# HB100_and_neo_m6.net
KiCad netlist of a schematic drawn in Altium Designer
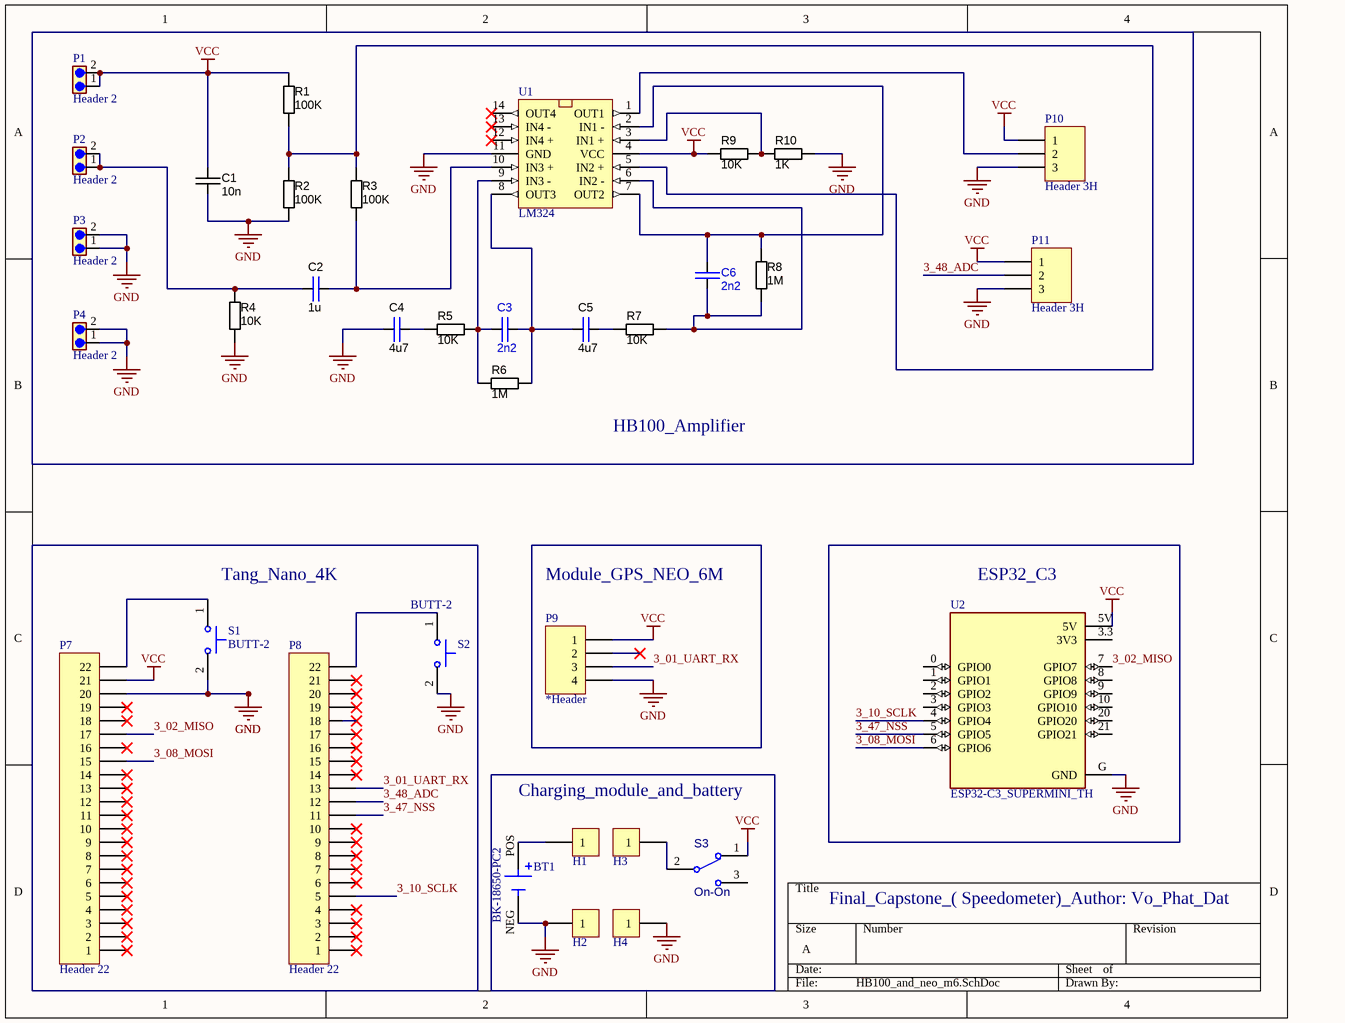
[diagram p0: HB100_and_neo_m6.SchDoc]

(export (version "E")
  (design (tool "Eeschema 10.0.6"))
  (components
    (comp (ref "BT1")
      (value "BK-18650-PC2")
      (footprint "BAT_BK-18650-PC2")
      (description "Battery Holder (Open) 18650 1 Cell PC Pin")
      (fields (field (name "MF") "MPD (Memory"))
      (libsource (lib "BK-18650-PC2") (part "BK-18650-PC2"))
    )
    (comp (ref "C1")
      (value "10n")
      (footprint "CAPC500P450250X550")
      (description "Capacitor Ceramic 220nF 10% 50V X7R radial 5mm lead spacing")
      (fields (field (name "TOLERANCE") "±10%") (field (name "Comment") "approved sub OK"))
      (libsource (lib "my Library") (part "CAPR_220n_Radial_5mm"))
    )
    (comp (ref "C2")
      (value "1u")
      (footprint "CAPC3216X180N")
      (description "Capacitor SMD Cer 220nF 10% 16V X7R 1206")
      (fields (field (name "TOLERANCE") "±10%") (field (name "Comment") "approved sub OK"))
      (libsource (lib "My library altium") (part "CAP C_1206"))
    )
    (comp (ref "C3")
      (value "2n2")
      (footprint "CAPC2012X135N")
      (description "Capacitor SMD Cer 1.8nF 10% 50V X7R 0805")
      (fields (field (name "TOLERANCE") "±10%") (field (name "Comment") "approved sub OK"))
      (libsource (lib "My library altium") (part "CAP C_0805"))
    )
    (comp (ref "C4")
      (value "4u7")
      (footprint "CAPC3216X180N")
      (description "Capacitor SMD Cer 220nF 10% 16V X7R 1206")
      (fields (field (name "TOLERANCE") "±10%") (field (name "Comment") "approved sub OK"))
      (libsource (lib "My library altium") (part "CAP C_1206"))
    )
    (comp (ref "C5")
      (value "4u7")
      (footprint "CAPC3216X180N")
      (description "Capacitor SMD Cer 220nF 10% 16V X7R 1206")
      (fields (field (name "TOLERANCE") "±10%") (field (name "Comment") "approved sub OK"))
      (libsource (lib "My library altium") (part "CAP C_1206"))
    )
    (comp (ref "C6")
      (value "2n2")
      (footprint "CAPC2012X135N")
      (description "Capacitor SMD Cer 1.8nF 10% 50V X7R 0805")
      (fields (field (name "TOLERANCE") "±10%") (field (name "Comment") "approved sub OK"))
      (libsource (lib "My library altium") (part "CAP C_0805"))
    )
    (comp (ref "H1")
      (value "Header 1")
      (footprint "HEAD1")
      (description "Header, 1-Pin, Right Angle")
      (fields (field (name "PUBLISHER") "Cynetik Group"))
      (libsource (lib "") (part "Header 1_1"))
    )
    (comp (ref "H2")
      (value "Header 1")
      (footprint "HEAD1")
      (description "Header, 1-Pin, Right Angle")
      (fields (field (name "PUBLISHER") "Cynetik Group"))
      (libsource (lib "") (part "Header 1_1"))
    )
    (comp (ref "H3")
      (value "Header 1")
      (footprint "HEAD1")
      (description "Header, 1-Pin, Right Angle")
      (fields (field (name "PUBLISHER") "Cynetik Group"))
      (libsource (lib "Cty1") (part "Header 1"))
    )
    (comp (ref "H4")
      (value "Header 1")
      (footprint "HEAD1")
      (description "Header, 1-Pin, Right Angle")
      (fields (field (name "PUBLISHER") "Cynetik Group"))
      (libsource (lib "Cty1") (part "Header 1"))
    )
    (comp (ref "P1")
      (value "Header 2")
      (footprint "61300211121")
      (fields (field (name "MF") "{'manufacturer': u'Wurth Electronics'}") (field (name "MP") "61300211121"))
      (libsource (lib "6130XX11121_61300211121") (part "6130XX11121_61300211121"))
    )
    (comp (ref "P2")
      (value "Header 2")
      (footprint "61300211121")
      (fields (field (name "MF") "{'manufacturer': u'Wurth Electronics'}") (field (name "MP") "61300211121"))
      (libsource (lib "6130XX11121_61300211121") (part "6130XX11121_61300211121"))
    )
    (comp (ref "P3")
      (value "Header 2")
      (footprint "61300211121")
      (fields (field (name "MF") "{'manufacturer': u'Wurth Electronics'}") (field (name "MP") "61300211121"))
      (libsource (lib "6130XX11121_61300211121") (part "6130XX11121_61300211121"))
    )
    (comp (ref "P4")
      (value "Header 2")
      (footprint "61300211121")
      (fields (field (name "MF") "{'manufacturer': u'Wurth Electronics'}") (field (name "MP") "61300211121"))
      (libsource (lib "6130XX11121_61300211121") (part "6130XX11121_61300211121"))
    )
    (comp (ref "P7")
      (value "Header 22")
      (footprint "HDR1X22")
      (description "Header, 22-Pin")
      (fields (field (name "PUBLISHER") "Altium Limited"))
      (libsource (lib "my Library") (part "Header 22"))
    )
    (comp (ref "P8")
      (value "Header 22")
      (footprint "HDR1X22")
      (description "Header, 22-Pin")
      (fields (field (name "PUBLISHER") "Altium Limited"))
      (libsource (lib "my Library") (part "Header 22"))
    )
    (comp (ref "P9")
      (value "*Header")
      (footprint "HDR1X4")
      (description "Header, 4-Pin, Right Angle")
      (fields (field (name "PUBLISHER") "Altium Limited"))
      (libsource (lib "Cty1") (part "Header 4"))
    )
    (comp (ref "P10")
      (value "Header 3H")
      (footprint "HDR1X3H")
      (description "Header, 3-Pin, Right Angle")
      (fields (field (name "PUBLISHER") "Altium Limited"))
      (libsource (lib "Cty1") (part "Header 3H"))
    )
    (comp (ref "P11")
      (value "Header 3H")
      (footprint "HDR1X3H")
      (description "Header, 3-Pin, Right Angle")
      (fields (field (name "PUBLISHER") "Altium Limited"))
      (libsource (lib "Cty1") (part "Header 3H"))
    )
    (comp (ref "R1")
      (value "100K")
      (footprint "RESC3216N_ZERO")
      (description "Resistor SMD chip 0.0 Ohm 0.25W 1206")
      (fields (field (name "TOLERANCE") "±5%") (field (name "Comment") "Thick Film"))
      (libsource (lib "My library altium") (part "RES_1206"))
    )
    (comp (ref "R2")
      (value "100K")
      (footprint "RESC3216N_ZERO")
      (description "Resistor SMD chip 0.0 Ohm 0.25W 1206")
      (fields (field (name "TOLERANCE") "±5%") (field (name "Comment") "Thick Film"))
      (libsource (lib "My library altium") (part "RES_1206"))
    )
    (comp (ref "R3")
      (value "100K")
      (footprint "RESC3216N_ZERO")
      (description "Resistor SMD chip 0.0 Ohm 0.25W 1206")
      (fields (field (name "TOLERANCE") "±5%") (field (name "Comment") "Thick Film"))
      (libsource (lib "My library altium") (part "RES_1206"))
    )
    (comp (ref "R4")
      (value "10K")
      (footprint "RESC3216N_ZERO")
      (description "Resistor SMD chip 0.0 Ohm 0.25W 1206")
      (fields (field (name "TOLERANCE") "±5%") (field (name "Comment") "Thick Film"))
      (libsource (lib "My library altium") (part "RES_1206"))
    )
    (comp (ref "R5")
      (value "10K")
      (footprint "RESC3216N_ZERO")
      (description "Resistor SMD chip 0.0 Ohm 0.25W 1206")
      (fields (field (name "TOLERANCE") "±5%") (field (name "Comment") "Thick Film"))
      (libsource (lib "") (part "RES_1206_1"))
    )
    (comp (ref "R6")
      (value "1M")
      (footprint "RESC3216N_ZERO")
      (description "Resistor SMD chip 0.0 Ohm 0.25W 1206")
      (fields (field (name "TOLERANCE") "±5%") (field (name "Comment") "Thick Film"))
      (libsource (lib "") (part "RES_1206_1"))
    )
    (comp (ref "R7")
      (value "10K")
      (footprint "RESC3216N_ZERO")
      (description "Resistor SMD chip 0.0 Ohm 0.25W 1206")
      (fields (field (name "TOLERANCE") "±5%") (field (name "Comment") "Thick Film"))
      (libsource (lib "") (part "RES_1206_1"))
    )
    (comp (ref "R8")
      (value "1M")
      (footprint "RESC3216N_ZERO")
      (description "Resistor SMD chip 0.0 Ohm 0.25W 1206")
      (fields (field (name "TOLERANCE") "±5%") (field (name "Comment") "Thick Film"))
      (libsource (lib "") (part "RES_1206_2"))
    )
    (comp (ref "R9")
      (value "10K")
      (footprint "RESC3216N_ZERO")
      (description "Resistor SMD chip 0.0 Ohm 0.25W 1206")
      (fields (field (name "TOLERANCE") "±5%") (field (name "Comment") "Thick Film"))
      (libsource (lib "") (part "RES_1206_1"))
    )
    (comp (ref "R10")
      (value "1K")
      (footprint "RESC3216N_ZERO")
      (description "Resistor SMD chip 0.0 Ohm 0.25W 1206")
      (fields (field (name "TOLERANCE") "±5%") (field (name "Comment") "Thick Film"))
      (libsource (lib "") (part "RES_1206_1"))
    )
    (comp (ref "S1")
      (value "BUTT-2")
      (footprint "SW_BUTT-2")
      (description "Tactile Switches MINI PUSH BUTTON SWITCH 2-PIN QTY. 4")
      (fields (field (name "MF") "Gravitech"))
      (libsource (lib "BUTT-2") (part "BUTT-2"))
    )
    (comp (ref "S2")
      (value "BUTT-2")
      (footprint "SW_BUTT-2")
      (description "Tactile Switches MINI PUSH BUTTON SWITCH 2-PIN QTY. 4")
      (fields (field (name "MF") "Gravitech"))
      (libsource (lib "BUTT-2") (part "BUTT-2"))
    )
    (comp (ref "S3")
      (value "ON-ON")
      (footprint "SWITCH_SPDT_SLIDER")
      (description "Switch THD vertical toggle SPDT")
      (fields (field (name "SWITCH FUNCTION") "On-On"))
      (libsource (lib "my Library") (part "SW_THD_SPDT_On-On"))
    )
    (comp (ref "U1")
      (value "LM324")
      (footprint "SOIC127P600X175-14N-LM324")
      (libsource (lib "My library altium") (part "LM324"))
    )
    (comp (ref "U2")
      (value "ESP32-C3_SUPERMINI_TH")
      (footprint "MODULE_ESP32-C3_SUPERMINI_TH")
      (description "Super tiny ESP32-C3 board")
      (fields (field (name "MF") "Espressif Systems") (field (name "MP") "ESP32-C3 SuperMini_TH"))
      (libsource (lib "ESP32-C3_SUPERMINI_TH") (part "ESP32-C3_SUPERMINI_TH"))
    )
  )
  (nets
    (net (code "1") (name "/3_01_UART_RX") (class "Default")
      (node (ref "P8") (pin "13") (pinfunction "13_13") (pintype "passive"))
      (node (ref "P9") (pin "3") (pinfunction "3_3") (pintype "passive"))
    )
    (net (code "2") (name "/3_02_MISO") (class "Default")
      (node (ref "P7") (pin "17") (pinfunction "17_17") (pintype "passive"))
      (node (ref "U2") (pin "7") (pinfunction "GPIO7_7") (pintype "bidirectional"))
    )
    (net (code "3") (name "/3_08_MOSI") (class "Default")
      (node (ref "P7") (pin "15") (pinfunction "15_15") (pintype "passive"))
      (node (ref "U2") (pin "6") (pinfunction "GPIO6_6") (pintype "bidirectional"))
    )
    (net (code "4") (name "/3_10_SCLK") (class "Default")
      (node (ref "P8") (pin "5") (pinfunction "5_5") (pintype "passive"))
      (node (ref "U2") (pin "4") (pinfunction "GPIO4_4") (pintype "bidirectional"))
    )
    (net (code "5") (name "/3_47_NSS") (class "Default")
      (node (ref "P8") (pin "11") (pinfunction "11_11") (pintype "passive"))
      (node (ref "U2") (pin "5") (pinfunction "GPIO5_5") (pintype "bidirectional"))
    )
    (net (code "6") (name "/3_48_ADC") (class "Default")
      (node (ref "P11") (pin "2") (pinfunction "2_2") (pintype "passive"))
      (node (ref "P8") (pin "12") (pinfunction "12_12") (pintype "passive"))
    )
    (net (code "7") (name "GND") (class "Default")
      (node (ref "BT1") (pin "NEG") (pinfunction "NEG_NEG") (pintype "passive"))
      (node (ref "C1") (pin "1") (pintype "passive"))
      (node (ref "C4") (pin "1") (pintype "passive"))
      (node (ref "H2") (pin "1") (pinfunction "1_1") (pintype "passive"))
      (node (ref "H4") (pin "1") (pinfunction "1_1") (pintype "passive"))
      (node (ref "P10") (pin "3") (pinfunction "3_3") (pintype "passive"))
      (node (ref "P11") (pin "3") (pinfunction "3_3") (pintype "passive"))
      (node (ref "P3") (pin "1") (pinfunction "1_1") (pintype "passive"))
      (node (ref "P3") (pin "2") (pinfunction "2_2") (pintype "passive"))
      (node (ref "P4") (pin "1") (pinfunction "1_1") (pintype "passive"))
      (node (ref "P4") (pin "2") (pinfunction "2_2") (pintype "passive"))
      (node (ref "P7") (pin "20") (pinfunction "20_20") (pintype "passive"))
      (node (ref "P9") (pin "4") (pinfunction "4_4") (pintype "passive"))
      (node (ref "R10") (pin "2") (pinfunction "2_2") (pintype "passive"))
      (node (ref "R2") (pin "2") (pinfunction "2_2") (pintype "passive"))
      (node (ref "R4") (pin "2") (pinfunction "2_2") (pintype "passive"))
      (node (ref "S1") (pin "2") (pinfunction "2_2") (pintype "passive"))
      (node (ref "S2") (pin "2") (pinfunction "2_2") (pintype "passive"))
      (node (ref "U1") (pin "11") (pinfunction "GND_11") (pintype "power_in"))
      (node (ref "U2") (pin "G") (pinfunction "GND_G") (pintype "power_in"))
    )
    (net (code "8") (name "Net-(BT1-PadPOS)") (class "Default")
      (node (ref "BT1") (pin "POS") (pinfunction "POS_POS") (pintype "passive"))
      (node (ref "H1") (pin "1") (pinfunction "1_1") (pintype "passive"))
    )
    (net (code "9") (name "Net-(C2-Pad1)") (class "Default")
      (node (ref "C2") (pin "1") (pintype "passive"))
      (node (ref "P2") (pin "1") (pinfunction "1_1") (pintype "passive"))
      (node (ref "P2") (pin "2") (pinfunction "2_2") (pintype "passive"))
      (node (ref "R4") (pin "1") (pinfunction "1_1") (pintype "passive"))
    )
    (net (code "10") (name "Net-(C4-Pad2)") (class "Default")
      (node (ref "C4") (pin "2") (pintype "passive"))
      (node (ref "R5") (pin "1") (pinfunction "1_1") (pintype "passive"))
    )
    (net (code "11") (name "Net-(C5-Pad2)") (class "Default")
      (node (ref "C5") (pin "2") (pintype "passive"))
      (node (ref "R7") (pin "1") (pinfunction "1_1") (pintype "passive"))
    )
    (net (code "12") (name "Net-(H3-Pad1)") (class "Default")
      (node (ref "H3") (pin "1") (pinfunction "1_1") (pintype "passive"))
      (node (ref "S3") (pin "2") (pinfunction "2_2") (pintype "passive"))
    )
    (net (code "13") (name "Net-(P7-Pad22)") (class "Default")
      (node (ref "P7") (pin "22") (pinfunction "22_22") (pintype "passive"))
      (node (ref "S1") (pin "1") (pinfunction "1_1") (pintype "passive"))
    )
    (net (code "14") (name "Net-(P8-Pad22)") (class "Default")
      (node (ref "P8") (pin "22") (pinfunction "22_22") (pintype "passive"))
      (node (ref "S2") (pin "1") (pinfunction "1_1") (pintype "passive"))
    )
    (net (code "15") (name "Net-(U1-IN1_+)") (class "Default")
      (node (ref "R10") (pin "1") (pinfunction "1_1") (pintype "passive"))
      (node (ref "R9") (pin "2") (pinfunction "2_2") (pintype "passive"))
      (node (ref "U1") (pin "3") (pinfunction "IN1_+_3") (pintype "input"))
    )
    (net (code "16") (name "Net-(U1-IN1_-)") (class "Default")
      (node (ref "C6") (pin "1") (pintype "passive"))
      (node (ref "R8") (pin "2") (pinfunction "2_2") (pintype "passive"))
      (node (ref "U1") (pin "2") (pinfunction "IN1_-_2") (pintype "input"))
      (node (ref "U1") (pin "7") (pinfunction "OUT2_7") (pintype "output"))
    )
    (net (code "17") (name "Net-(U1-IN2_+)") (class "Default")
      (node (ref "R1") (pin "2") (pinfunction "2_2") (pintype "passive"))
      (node (ref "R2") (pin "1") (pinfunction "1_1") (pintype "passive"))
      (node (ref "R3") (pin "1") (pinfunction "1_1") (pintype "passive"))
      (node (ref "U1") (pin "5") (pinfunction "IN2_+_5") (pintype "input"))
    )
    (net (code "18") (name "Net-(U1-IN2_-)") (class "Default")
      (node (ref "C6") (pin "2") (pintype "passive"))
      (node (ref "R7") (pin "2") (pinfunction "2_2") (pintype "passive"))
      (node (ref "R8") (pin "1") (pinfunction "1_1") (pintype "passive"))
      (node (ref "U1") (pin "6") (pinfunction "IN2_-_6") (pintype "input"))
    )
    (net (code "19") (name "Net-(U1-IN3_+)") (class "Default")
      (node (ref "C2") (pin "2") (pintype "passive"))
      (node (ref "R3") (pin "2") (pinfunction "2_2") (pintype "passive"))
      (node (ref "U1") (pin "10") (pinfunction "IN3_+_10") (pintype "input"))
    )
    (net (code "20") (name "Net-(U1-IN3_-)") (class "Default")
      (node (ref "C3") (pin "1") (pintype "passive"))
      (node (ref "R5") (pin "2") (pinfunction "2_2") (pintype "passive"))
      (node (ref "R6") (pin "1") (pinfunction "1_1") (pintype "passive"))
      (node (ref "U1") (pin "9") (pinfunction "IN3_-_9") (pintype "input"))
    )
    (net (code "21") (name "Net-(U1-OUT1)") (class "Default")
      (node (ref "P10") (pin "2") (pinfunction "2_2") (pintype "passive"))
      (node (ref "U1") (pin "1") (pinfunction "OUT1_1") (pintype "output"))
    )
    (net (code "22") (name "Net-(U1-OUT3)") (class "Default")
      (node (ref "C3") (pin "2") (pintype "passive"))
      (node (ref "C5") (pin "1") (pintype "passive"))
      (node (ref "R6") (pin "2") (pinfunction "2_2") (pintype "passive"))
      (node (ref "U1") (pin "8") (pinfunction "OUT3_8") (pintype "output"))
    )
    (net (code "23") (name "VCC") (class "Default")
      (node (ref "C1") (pin "2") (pintype "passive"))
      (node (ref "P1") (pin "1") (pinfunction "1_1") (pintype "passive"))
      (node (ref "P1") (pin "2") (pinfunction "2_2") (pintype "passive"))
      (node (ref "P10") (pin "1") (pinfunction "1_1") (pintype "passive"))
      (node (ref "P11") (pin "1") (pinfunction "1_1") (pintype "passive"))
      (node (ref "P7") (pin "21") (pinfunction "21_21") (pintype "passive"))
      (node (ref "P9") (pin "1") (pinfunction "1_1") (pintype "passive"))
      (node (ref "R1") (pin "1") (pinfunction "1_1") (pintype "passive"))
      (node (ref "R9") (pin "1") (pinfunction "1_1") (pintype "passive"))
      (node (ref "S3") (pin "1") (pinfunction "1_1") (pintype "passive"))
      (node (ref "U1") (pin "4") (pinfunction "VCC_4") (pintype "power_in"))
      (node (ref "U2") (pin "5V") (pinfunction "5V_5V") (pintype "power_in"))
    )
    (net (code "24") (name "unconnected-(P7-Pad1)") (class "Default")
      (node (ref "P7") (pin "1") (pinfunction "1_1") (pintype "passive+no_connect"))
    )
    (net (code "25") (name "unconnected-(P7-Pad2)") (class "Default")
      (node (ref "P7") (pin "2") (pinfunction "2_2") (pintype "passive+no_connect"))
    )
    (net (code "26") (name "unconnected-(P7-Pad3)") (class "Default")
      (node (ref "P7") (pin "3") (pinfunction "3_3") (pintype "passive+no_connect"))
    )
    (net (code "27") (name "unconnected-(P7-Pad4)") (class "Default")
      (node (ref "P7") (pin "4") (pinfunction "4_4") (pintype "passive+no_connect"))
    )
    (net (code "28") (name "unconnected-(P7-Pad5)") (class "Default")
      (node (ref "P7") (pin "5") (pinfunction "5_5") (pintype "passive+no_connect"))
    )
    (net (code "29") (name "unconnected-(P7-Pad6)") (class "Default")
      (node (ref "P7") (pin "6") (pinfunction "6_6") (pintype "passive+no_connect"))
    )
    (net (code "30") (name "unconnected-(P7-Pad7)") (class "Default")
      (node (ref "P7") (pin "7") (pinfunction "7_7") (pintype "passive+no_connect"))
    )
    (net (code "31") (name "unconnected-(P7-Pad8)") (class "Default")
      (node (ref "P7") (pin "8") (pinfunction "8_8") (pintype "passive+no_connect"))
    )
    (net (code "32") (name "unconnected-(P7-Pad9)") (class "Default")
      (node (ref "P7") (pin "9") (pinfunction "9_9") (pintype "passive+no_connect"))
    )
    (net (code "33") (name "unconnected-(P7-Pad10)") (class "Default")
      (node (ref "P7") (pin "10") (pinfunction "10_10") (pintype "passive+no_connect"))
    )
    (net (code "34") (name "unconnected-(P7-Pad11)") (class "Default")
      (node (ref "P7") (pin "11") (pinfunction "11_11") (pintype "passive+no_connect"))
    )
    (net (code "35") (name "unconnected-(P7-Pad12)") (class "Default")
      (node (ref "P7") (pin "12") (pinfunction "12_12") (pintype "passive+no_connect"))
    )
    (net (code "36") (name "unconnected-(P7-Pad13)") (class "Default")
      (node (ref "P7") (pin "13") (pinfunction "13_13") (pintype "passive+no_connect"))
    )
    (net (code "37") (name "unconnected-(P7-Pad14)") (class "Default")
      (node (ref "P7") (pin "14") (pinfunction "14_14") (pintype "passive+no_connect"))
    )
    (net (code "38") (name "unconnected-(P7-Pad16)") (class "Default")
      (node (ref "P7") (pin "16") (pinfunction "16_16") (pintype "passive+no_connect"))
    )
    (net (code "39") (name "unconnected-(P7-Pad18)") (class "Default")
      (node (ref "P7") (pin "18") (pinfunction "18_18") (pintype "passive+no_connect"))
    )
    (net (code "40") (name "unconnected-(P7-Pad19)") (class "Default")
      (node (ref "P7") (pin "19") (pinfunction "19_19") (pintype "passive+no_connect"))
    )
    (net (code "41") (name "unconnected-(P8-Pad1)") (class "Default")
      (node (ref "P8") (pin "1") (pinfunction "1_1") (pintype "passive+no_connect"))
    )
    (net (code "42") (name "unconnected-(P8-Pad2)") (class "Default")
      (node (ref "P8") (pin "2") (pinfunction "2_2") (pintype "passive+no_connect"))
    )
    (net (code "43") (name "unconnected-(P8-Pad3)") (class "Default")
      (node (ref "P8") (pin "3") (pinfunction "3_3") (pintype "passive+no_connect"))
    )
    (net (code "44") (name "unconnected-(P8-Pad4)") (class "Default")
      (node (ref "P8") (pin "4") (pinfunction "4_4") (pintype "passive+no_connect"))
    )
    (net (code "45") (name "unconnected-(P8-Pad6)") (class "Default")
      (node (ref "P8") (pin "6") (pinfunction "6_6") (pintype "passive+no_connect"))
    )
    (net (code "46") (name "unconnected-(P8-Pad7)") (class "Default")
      (node (ref "P8") (pin "7") (pinfunction "7_7") (pintype "passive+no_connect"))
    )
    (net (code "47") (name "unconnected-(P8-Pad8)") (class "Default")
      (node (ref "P8") (pin "8") (pinfunction "8_8") (pintype "passive+no_connect"))
    )
    (net (code "48") (name "unconnected-(P8-Pad9)") (class "Default")
      (node (ref "P8") (pin "9") (pinfunction "9_9") (pintype "passive+no_connect"))
    )
    (net (code "49") (name "unconnected-(P8-Pad10)") (class "Default")
      (node (ref "P8") (pin "10") (pinfunction "10_10") (pintype "passive+no_connect"))
    )
    (net (code "50") (name "unconnected-(P8-Pad14)") (class "Default")
      (node (ref "P8") (pin "14") (pinfunction "14_14") (pintype "passive+no_connect"))
    )
    (net (code "51") (name "unconnected-(P8-Pad15)") (class "Default")
      (node (ref "P8") (pin "15") (pinfunction "15_15") (pintype "passive+no_connect"))
    )
    (net (code "52") (name "unconnected-(P8-Pad16)") (class "Default")
      (node (ref "P8") (pin "16") (pinfunction "16_16") (pintype "passive+no_connect"))
    )
    (net (code "53") (name "unconnected-(P8-Pad17)") (class "Default")
      (node (ref "P8") (pin "17") (pinfunction "17_17") (pintype "passive+no_connect"))
    )
    (net (code "54") (name "unconnected-(P8-Pad18)") (class "Default")
      (node (ref "P8") (pin "18") (pinfunction "18_18") (pintype "passive+no_connect"))
    )
    (net (code "55") (name "unconnected-(P8-Pad19)") (class "Default")
      (node (ref "P8") (pin "19") (pinfunction "19_19") (pintype "passive+no_connect"))
    )
    (net (code "56") (name "unconnected-(P8-Pad20)") (class "Default")
      (node (ref "P8") (pin "20") (pinfunction "20_20") (pintype "passive+no_connect"))
    )
    (net (code "57") (name "unconnected-(P8-Pad21)") (class "Default")
      (node (ref "P8") (pin "21") (pinfunction "21_21") (pintype "passive+no_connect"))
    )
    (net (code "58") (name "unconnected-(P9-Pad2)") (class "Default")
      (node (ref "P9") (pin "2") (pinfunction "2_2") (pintype "passive+no_connect"))
    )
    (net (code "59") (name "unconnected-(S3-Pad3)") (class "Default")
      (node (ref "S3") (pin "3") (pinfunction "3_3") (pintype "passive"))
    )
    (net (code "60") (name "unconnected-(U1-IN4_+-Pad12)") (class "Default")
      (node (ref "U1") (pin "12") (pinfunction "IN4_+_12") (pintype "input+no_connect"))
    )
    (net (code "61") (name "unconnected-(U1-IN4_--Pad13)") (class "Default")
      (node (ref "U1") (pin "13") (pinfunction "IN4_-_13") (pintype "input+no_connect"))
    )
    (net (code "62") (name "unconnected-(U1-OUT4-Pad14)") (class "Default")
      (node (ref "U1") (pin "14") (pinfunction "OUT4_14") (pintype "output+no_connect"))
    )
    (net (code "63") (name "unconnected-(U2-3V3-Pad3.3)") (class "Default")
      (node (ref "U2") (pin "3.3") (pinfunction "3V3_3.3") (pintype "power_in"))
    )
    (net (code "64") (name "unconnected-(U2-GPIO0-Pad0)") (class "Default")
      (node (ref "U2") (pin "0") (pinfunction "GPIO0_0") (pintype "bidirectional"))
    )
    (net (code "65") (name "unconnected-(U2-GPIO1-Pad1)") (class "Default")
      (node (ref "U2") (pin "1") (pinfunction "GPIO1_1") (pintype "bidirectional"))
    )
    (net (code "66") (name "unconnected-(U2-GPIO2-Pad2)") (class "Default")
      (node (ref "U2") (pin "2") (pinfunction "GPIO2_2") (pintype "bidirectional"))
    )
    (net (code "67") (name "unconnected-(U2-GPIO3-Pad3)") (class "Default")
      (node (ref "U2") (pin "3") (pinfunction "GPIO3_3") (pintype "bidirectional"))
    )
    (net (code "68") (name "unconnected-(U2-GPIO8-Pad8)") (class "Default")
      (node (ref "U2") (pin "8") (pinfunction "GPIO8_8") (pintype "bidirectional"))
    )
    (net (code "69") (name "unconnected-(U2-GPIO9-Pad9)") (class "Default")
      (node (ref "U2") (pin "9") (pinfunction "GPIO9_9") (pintype "bidirectional"))
    )
    (net (code "70") (name "unconnected-(U2-GPIO10-Pad10)") (class "Default")
      (node (ref "U2") (pin "10") (pinfunction "GPIO10_10") (pintype "bidirectional"))
    )
    (net (code "71") (name "unconnected-(U2-GPIO20-Pad20)") (class "Default")
      (node (ref "U2") (pin "20") (pinfunction "GPIO20_20") (pintype "bidirectional"))
    )
    (net (code "72") (name "unconnected-(U2-GPIO21-Pad21)") (class "Default")
      (node (ref "U2") (pin "21") (pinfunction "GPIO21_21") (pintype "bidirectional"))
    )
  )
)
